# unbiased_electronic_dice.net
KiCad netlist of a schematic drawn in EAGLE
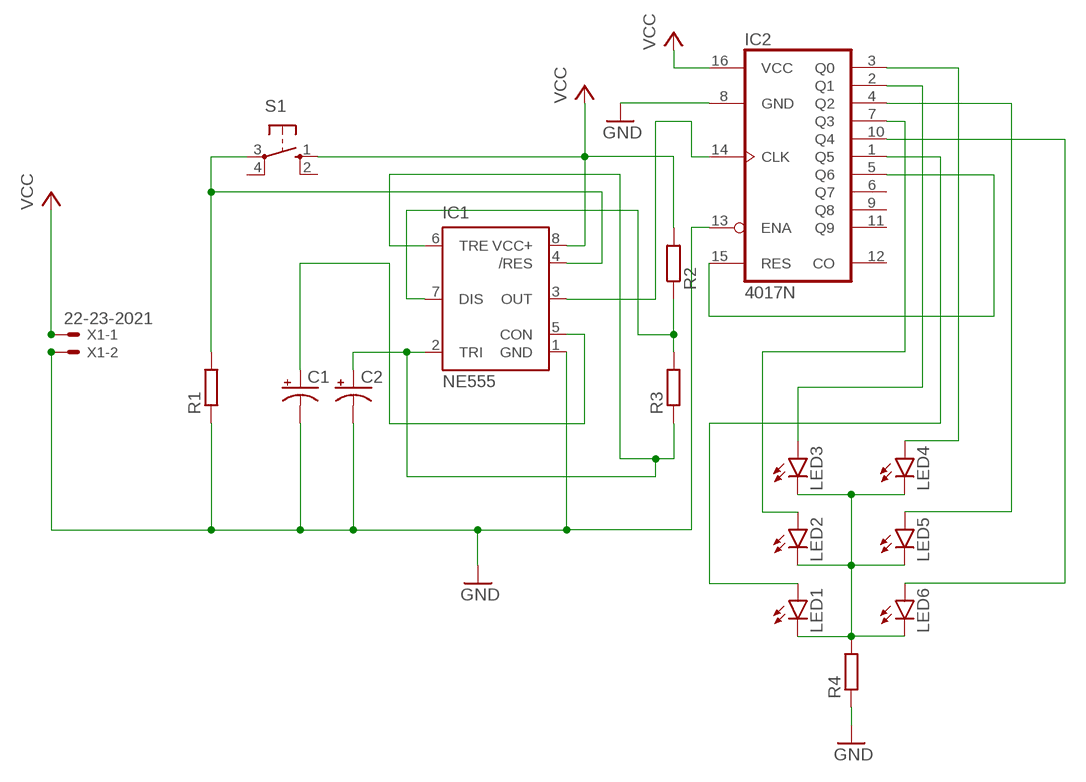
[diagram p0: schematic, sheet 1]

(export (version "E")
  (design (tool "Eeschema 10.0.6"))
  (components
    (comp (ref "C1")
      (value "CPOL-USE2,5-6E")
      (footprint "eagle-import:E2,5-6E")
      (libsource (lib "eagle-import") (part "CPOL-USE2,5-6E"))
    )
    (comp (ref "C2")
      (value "CPOL-USE2,5-6E")
      (footprint "eagle-import:E2,5-6E")
      (libsource (lib "eagle-import") (part "CPOL-USE2,5-6E"))
    )
    (comp (ref "IC1")
      (value "NE555")
      (footprint "eagle-import:DIL-08")
      (fields
        (field (name "MF") "Arrow Electronics")
        (field (name "MPN") "NE555N")
        (field (name "MF_1") "STMICROELECTRONICS")
      )
      (libsource (lib "eagle-import") (part "NE555"))
    )
    (comp (ref "IC2")
      (value "4017N")
      (footprint "eagle-import:DIL16")
      (libsource (lib "eagle-import") (part "4017N"))
    )
    (comp (ref "LED1")
      (value "LED5MM")
      (footprint "eagle-import:LED5MM")
      (libsource (lib "eagle-import") (part "LED5MM"))
    )
    (comp (ref "LED2")
      (value "LED5MM")
      (footprint "eagle-import:LED5MM")
      (libsource (lib "eagle-import") (part "LED5MM"))
    )
    (comp (ref "LED3")
      (value "LED5MM")
      (footprint "eagle-import:LED5MM")
      (libsource (lib "eagle-import") (part "LED5MM"))
    )
    (comp (ref "LED4")
      (value "LED5MM")
      (footprint "eagle-import:LED5MM")
      (libsource (lib "eagle-import") (part "LED5MM"))
    )
    (comp (ref "LED5")
      (value "LED5MM")
      (footprint "eagle-import:LED5MM")
      (libsource (lib "eagle-import") (part "LED5MM"))
    )
    (comp (ref "LED6")
      (value "LED5MM")
      (footprint "eagle-import:LED5MM")
      (libsource (lib "eagle-import") (part "LED5MM"))
    )
    (comp (ref "R1")
      (value "R-EU_0207/15")
      (footprint "eagle-import:0207_15")
      (fields (field (name "MF") "AMPHENOL INDUSTRIAL") (field (name "MPN") "MS27474E20F16P"))
      (libsource (lib "eagle-import") (part "R-EU_0207/15"))
    )
    (comp (ref "R2")
      (value "R-EU_0207/15")
      (footprint "eagle-import:0207_15")
      (fields (field (name "MF") "AMPHENOL INDUSTRIAL") (field (name "MPN") "MS27474E20F16P"))
      (libsource (lib "eagle-import") (part "R-EU_0207/15"))
    )
    (comp (ref "R3")
      (value "R-EU_0207/15")
      (footprint "eagle-import:0207_15")
      (fields (field (name "MF") "AMPHENOL INDUSTRIAL") (field (name "MPN") "MS27474E20F16P"))
      (libsource (lib "eagle-import") (part "R-EU_0207/15"))
    )
    (comp (ref "R4")
      (value "R-EU_0207/7")
      (footprint "eagle-import:0207_7")
      (libsource (lib "eagle-import") (part "R-EU_0207/7"))
    )
    (comp (ref "S1")
      (value "10-XX")
      (footprint "eagle-import:B3F-10XX")
      (fields (field (name "MPN") "B3F-1000"))
      (libsource (lib "eagle-import") (part "10-XX"))
    )
    (comp (ref "X1")
      (value "22-23-2021")
      (footprint "eagle-import:22-23-2021")
      (fields (field (name "MF") "MOLEX"))
      (libsource (lib "eagle-import") (part "22-23-2021"))
    )
  )
  (nets
    (net (code "1") (name "GND") (class "Default")
      (node (ref "C1") (pin "-") (pinfunction "-_-") (pintype "passive"))
      (node (ref "C2") (pin "-") (pinfunction "-_-") (pintype "passive"))
      (node (ref "IC1") (pin "1") (pinfunction "GND_1") (pintype "power_in"))
      (node (ref "IC2") (pin "13") (pinfunction "ENA_13") (pintype "input"))
      (node (ref "IC2") (pin "8") (pinfunction "GND_8") (pintype "power_in"))
      (node (ref "R1") (pin "1") (pinfunction "1_1") (pintype "passive"))
      (node (ref "R4") (pin "1") (pinfunction "1_1") (pintype "passive"))
      (node (ref "X1") (pin "2") (pinfunction "S_2") (pintype "passive"))
    )
    (net (code "2") (name "Net-(IC1-CON)") (class "Default")
      (node (ref "C1") (pin "+") (pinfunction "+_+") (pintype "passive"))
      (node (ref "IC1") (pin "5") (pinfunction "CON_5") (pintype "input"))
    )
    (net (code "3") (name "Net-(IC1-DIS)") (class "Default")
      (node (ref "IC1") (pin "7") (pinfunction "DIS_7") (pintype "input"))
      (node (ref "R2") (pin "1") (pinfunction "1_1") (pintype "passive"))
      (node (ref "R3") (pin "2") (pinfunction "2_2") (pintype "passive"))
    )
    (net (code "4") (name "Net-(IC1-OUT)") (class "Default")
      (node (ref "IC1") (pin "3") (pinfunction "OUT_3") (pintype "output"))
      (node (ref "IC2") (pin "14") (pinfunction "CLK_14") (pintype "input"))
    )
    (net (code "5") (name "Net-(IC1-TRE)") (class "Default")
      (node (ref "C2") (pin "+") (pinfunction "+_+") (pintype "passive"))
      (node (ref "IC1") (pin "2") (pinfunction "TRI_2") (pintype "input"))
      (node (ref "IC1") (pin "6") (pinfunction "TRE_6") (pintype "input"))
      (node (ref "R3") (pin "1") (pinfunction "1_1") (pintype "passive"))
    )
    (net (code "6") (name "Net-(IC1-{slash}RES)") (class "Default")
      (node (ref "IC1") (pin "4") (pinfunction "/RES_4") (pintype "input"))
      (node (ref "R1") (pin "2") (pinfunction "2_2") (pintype "passive"))
      (node (ref "S1") (pin "3") (pinfunction "P_3") (pintype "passive"))
    )
    (net (code "7") (name "Net-(IC2-Q0)") (class "Default")
      (node (ref "IC2") (pin "3") (pinfunction "Q0_3") (pintype "output"))
      (node (ref "LED4") (pin "A") (pinfunction "A_A") (pintype "passive"))
    )
    (net (code "8") (name "Net-(IC2-Q1)") (class "Default")
      (node (ref "IC2") (pin "2") (pinfunction "Q1_2") (pintype "output"))
      (node (ref "LED3") (pin "A") (pinfunction "A_A") (pintype "passive"))
    )
    (net (code "9") (name "Net-(IC2-Q2)") (class "Default")
      (node (ref "IC2") (pin "4") (pinfunction "Q2_4") (pintype "output"))
      (node (ref "LED5") (pin "A") (pinfunction "A_A") (pintype "passive"))
    )
    (net (code "10") (name "Net-(IC2-Q3)") (class "Default")
      (node (ref "IC2") (pin "7") (pinfunction "Q3_7") (pintype "output"))
      (node (ref "LED2") (pin "A") (pinfunction "A_A") (pintype "passive"))
    )
    (net (code "11") (name "Net-(IC2-Q4)") (class "Default")
      (node (ref "IC2") (pin "10") (pinfunction "Q4_10") (pintype "output"))
      (node (ref "LED6") (pin "A") (pinfunction "A_A") (pintype "passive"))
    )
    (net (code "12") (name "Net-(IC2-Q5)") (class "Default")
      (node (ref "IC2") (pin "1") (pinfunction "Q5_1") (pintype "output"))
      (node (ref "LED1") (pin "A") (pinfunction "A_A") (pintype "passive"))
    )
    (net (code "13") (name "Net-(IC2-Q6)") (class "Default")
      (node (ref "IC2") (pin "15") (pinfunction "RES_15") (pintype "input"))
      (node (ref "IC2") (pin "5") (pinfunction "Q6_5") (pintype "output"))
    )
    (net (code "14") (name "Net-(LED1-C)") (class "Default")
      (node (ref "LED1") (pin "K") (pinfunction "C_K") (pintype "passive"))
      (node (ref "LED2") (pin "K") (pinfunction "C_K") (pintype "passive"))
      (node (ref "LED3") (pin "K") (pinfunction "C_K") (pintype "passive"))
      (node (ref "LED4") (pin "K") (pinfunction "C_K") (pintype "passive"))
      (node (ref "LED5") (pin "K") (pinfunction "C_K") (pintype "passive"))
      (node (ref "LED6") (pin "K") (pinfunction "C_K") (pintype "passive"))
      (node (ref "R4") (pin "2") (pinfunction "2_2") (pintype "passive"))
    )
    (net (code "15") (name "VCC") (class "Default")
      (node (ref "IC1") (pin "8") (pinfunction "VCC+_8") (pintype "power_in"))
      (node (ref "IC2") (pin "16") (pinfunction "VCC_16") (pintype "power_in"))
      (node (ref "R2") (pin "2") (pinfunction "2_2") (pintype "passive"))
      (node (ref "S1") (pin "1") (pinfunction "S_1") (pintype "passive"))
      (node (ref "X1") (pin "1") (pinfunction "S_1") (pintype "passive"))
    )
    (net (code "16") (name "unconnected-(IC2-CO-Pad12)") (class "Default")
      (node (ref "IC2") (pin "12") (pinfunction "CO_12") (pintype "output"))
    )
    (net (code "17") (name "unconnected-(IC2-Q7-Pad6)") (class "Default")
      (node (ref "IC2") (pin "6") (pinfunction "Q7_6") (pintype "output"))
    )
    (net (code "18") (name "unconnected-(IC2-Q8-Pad9)") (class "Default")
      (node (ref "IC2") (pin "9") (pinfunction "Q8_9") (pintype "output"))
    )
    (net (code "19") (name "unconnected-(IC2-Q9-Pad11)") (class "Default")
      (node (ref "IC2") (pin "11") (pinfunction "Q9_11") (pintype "output"))
    )
    (net (code "20") (name "unconnected-(S1-P1-Pad4)") (class "Default")
      (node (ref "S1") (pin "4") (pinfunction "P1_4") (pintype "passive"))
    )
    (net (code "21") (name "unconnected-(S1-S1-Pad2)") (class "Default")
      (node (ref "S1") (pin "2") (pinfunction "S1_2") (pintype "passive"))
    )
  )
)
